# busstop.net
KiCad netlist of a schematic drawn in EAGLE
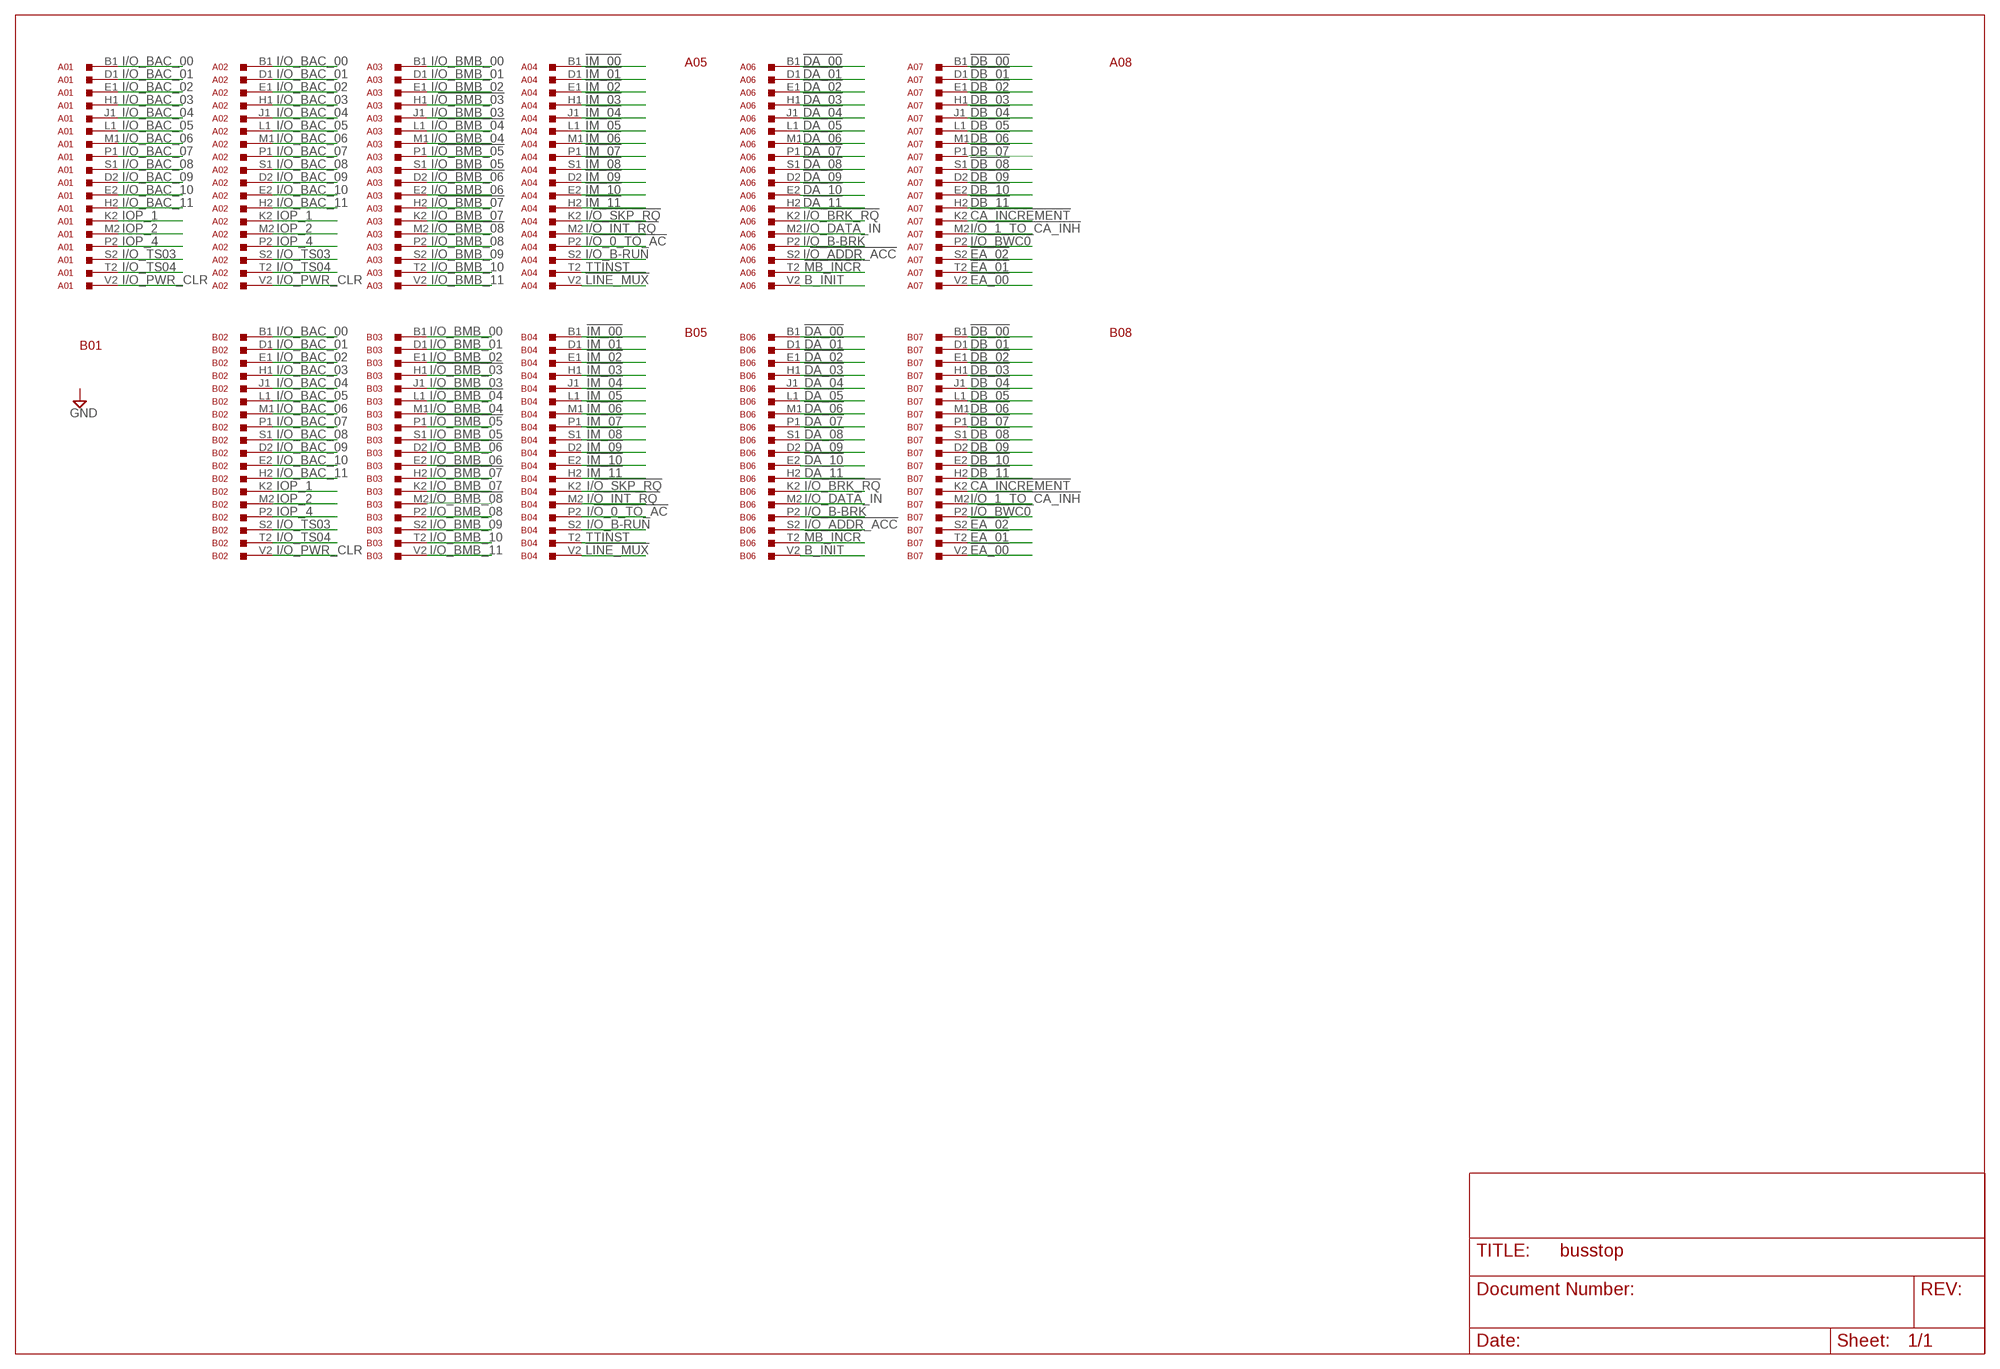
[diagram p0: schematic, sheet 1]

(export (version "E")
  (design (tool "Eeschema 10.0.6"))
  (components
    (comp (ref "A01")
      (value "G717")
      (footprint "eagle-import:H807")
      (libsource (lib "eagle-import") (part "M903"))
    )
    (comp (ref "A02")
      (value "M903")
      (footprint "eagle-import:H807")
      (libsource (lib "eagle-import") (part "M903"))
    )
    (comp (ref "A03")
      (value "M903")
      (footprint "eagle-import:H807")
      (libsource (lib "eagle-import") (part "M903"))
    )
    (comp (ref "A04")
      (value "M903")
      (footprint "eagle-import:H807")
      (libsource (lib "eagle-import") (part "M903"))
    )
    (comp (ref "A05")
      (value "H807")
      (footprint "eagle-import:H807")
      (libsource (lib "eagle-import") (part "H807"))
    )
    (comp (ref "A06")
      (value "M903")
      (footprint "eagle-import:H807")
      (libsource (lib "eagle-import") (part "M903"))
    )
    (comp (ref "A07")
      (value "M903")
      (footprint "eagle-import:H807")
      (libsource (lib "eagle-import") (part "M903"))
    )
    (comp (ref "A08")
      (value "H807")
      (footprint "eagle-import:H807")
      (libsource (lib "eagle-import") (part "H807"))
    )
    (comp (ref "B01")
      (value "H807")
      (footprint "eagle-import:H807")
      (libsource (lib "eagle-import") (part "H807"))
    )
    (comp (ref "B02")
      (value "M903")
      (footprint "eagle-import:H807")
      (libsource (lib "eagle-import") (part "M903"))
    )
    (comp (ref "B03")
      (value "M903")
      (footprint "eagle-import:H807")
      (libsource (lib "eagle-import") (part "M903"))
    )
    (comp (ref "B04")
      (value "M903")
      (footprint "eagle-import:H807")
      (libsource (lib "eagle-import") (part "M903"))
    )
    (comp (ref "B05")
      (value "H807")
      (footprint "eagle-import:H807")
      (libsource (lib "eagle-import") (part "H807"))
    )
    (comp (ref "B06")
      (value "M903")
      (footprint "eagle-import:H807")
      (libsource (lib "eagle-import") (part "M903"))
    )
    (comp (ref "B07")
      (value "M903")
      (footprint "eagle-import:H807")
      (libsource (lib "eagle-import") (part "M903"))
    )
    (comp (ref "B08")
      (value "H807")
      (footprint "eagle-import:H807")
      (libsource (lib "eagle-import") (part "H807"))
    )
  )
  (nets
    (net (code "1") (name "/B_INIT") (class "Default")
      (node (ref "A06") (pin "V2") (pinfunction "P$2_V2") (pintype "bidirectional"))
      (node (ref "B06") (pin "V2") (pinfunction "P$2_V2") (pintype "bidirectional"))
    )
    (net (code "2") (name "/IOP_1") (class "Default")
      (node (ref "A01") (pin "K2") (pinfunction "P$2_K2") (pintype "bidirectional"))
      (node (ref "A02") (pin "K2") (pinfunction "P$2_K2") (pintype "bidirectional"))
      (node (ref "B02") (pin "K2") (pinfunction "P$2_K2") (pintype "bidirectional"))
    )
    (net (code "3") (name "/IOP_2") (class "Default")
      (node (ref "A01") (pin "M2") (pinfunction "P$2_M2") (pintype "bidirectional"))
      (node (ref "A02") (pin "M2") (pinfunction "P$2_M2") (pintype "bidirectional"))
      (node (ref "B02") (pin "M2") (pinfunction "P$2_M2") (pintype "bidirectional"))
    )
    (net (code "4") (name "/IOP_4") (class "Default")
      (node (ref "A01") (pin "P2") (pinfunction "P$2_P2") (pintype "bidirectional"))
      (node (ref "A02") (pin "P2") (pinfunction "P$2_P2") (pintype "bidirectional"))
      (node (ref "B02") (pin "P2") (pinfunction "P$2_P2") (pintype "bidirectional"))
    )
    (net (code "5") (name "/I{slash}O_B-BRK") (class "Default")
      (node (ref "A06") (pin "P2") (pinfunction "P$2_P2") (pintype "bidirectional"))
      (node (ref "B06") (pin "P2") (pinfunction "P$2_P2") (pintype "bidirectional"))
    )
    (net (code "6") (name "/I{slash}O_B-RUN") (class "Default")
      (node (ref "A04") (pin "S2") (pinfunction "P$2_S2") (pintype "bidirectional"))
      (node (ref "B04") (pin "S2") (pinfunction "P$2_S2") (pintype "bidirectional"))
    )
    (net (code "7") (name "/I{slash}O_BAC_00") (class "Default")
      (node (ref "A01") (pin "B1") (pinfunction "P$2_B1") (pintype "bidirectional"))
      (node (ref "A02") (pin "B1") (pinfunction "P$2_B1") (pintype "bidirectional"))
      (node (ref "B02") (pin "B1") (pinfunction "P$2_B1") (pintype "bidirectional"))
    )
    (net (code "8") (name "/I{slash}O_BAC_01") (class "Default")
      (node (ref "A01") (pin "D1") (pinfunction "P$2_D1") (pintype "bidirectional"))
      (node (ref "A02") (pin "D1") (pinfunction "P$2_D1") (pintype "bidirectional"))
      (node (ref "B02") (pin "D1") (pinfunction "P$2_D1") (pintype "bidirectional"))
    )
    (net (code "9") (name "/I{slash}O_BAC_02") (class "Default")
      (node (ref "A01") (pin "E1") (pinfunction "P$2_E1") (pintype "bidirectional"))
      (node (ref "A02") (pin "E1") (pinfunction "P$2_E1") (pintype "bidirectional"))
      (node (ref "B02") (pin "E1") (pinfunction "P$2_E1") (pintype "bidirectional"))
    )
    (net (code "10") (name "/I{slash}O_BAC_03") (class "Default")
      (node (ref "A01") (pin "H1") (pinfunction "P$2_H1") (pintype "bidirectional"))
      (node (ref "A02") (pin "H1") (pinfunction "P$2_H1") (pintype "bidirectional"))
      (node (ref "B02") (pin "H1") (pinfunction "P$2_H1") (pintype "bidirectional"))
    )
    (net (code "11") (name "/I{slash}O_BAC_04") (class "Default")
      (node (ref "A01") (pin "J1") (pinfunction "P$2_J1") (pintype "bidirectional"))
      (node (ref "A02") (pin "J1") (pinfunction "P$2_J1") (pintype "bidirectional"))
      (node (ref "B02") (pin "J1") (pinfunction "P$2_J1") (pintype "bidirectional"))
    )
    (net (code "12") (name "/I{slash}O_BAC_05") (class "Default")
      (node (ref "A01") (pin "L1") (pinfunction "P$2_L1") (pintype "bidirectional"))
      (node (ref "A02") (pin "L1") (pinfunction "P$2_L1") (pintype "bidirectional"))
      (node (ref "B02") (pin "L1") (pinfunction "P$2_L1") (pintype "bidirectional"))
    )
    (net (code "13") (name "/I{slash}O_BAC_06") (class "Default")
      (node (ref "A01") (pin "M1") (pinfunction "P$2_M1") (pintype "bidirectional"))
      (node (ref "A02") (pin "M1") (pinfunction "P$2_M1") (pintype "bidirectional"))
      (node (ref "B02") (pin "M1") (pinfunction "P$2_M1") (pintype "bidirectional"))
    )
    (net (code "14") (name "/I{slash}O_BAC_07") (class "Default")
      (node (ref "A01") (pin "P1") (pinfunction "P$2_P1") (pintype "bidirectional"))
      (node (ref "A02") (pin "P1") (pinfunction "P$2_P1") (pintype "bidirectional"))
      (node (ref "B02") (pin "P1") (pinfunction "P$2_P1") (pintype "bidirectional"))
    )
    (net (code "15") (name "/I{slash}O_BAC_08") (class "Default")
      (node (ref "A01") (pin "S1") (pinfunction "P$2_S1") (pintype "bidirectional"))
      (node (ref "A02") (pin "S1") (pinfunction "P$2_S1") (pintype "bidirectional"))
      (node (ref "B02") (pin "S1") (pinfunction "P$2_S1") (pintype "bidirectional"))
    )
    (net (code "16") (name "/I{slash}O_BAC_09") (class "Default")
      (node (ref "A01") (pin "D2") (pinfunction "P$2_D2") (pintype "bidirectional"))
      (node (ref "A02") (pin "D2") (pinfunction "P$2_D2") (pintype "bidirectional"))
      (node (ref "B02") (pin "D2") (pinfunction "P$2_D2") (pintype "bidirectional"))
    )
    (net (code "17") (name "/I{slash}O_BAC_10") (class "Default")
      (node (ref "A01") (pin "E2") (pinfunction "P$2_E2") (pintype "bidirectional"))
      (node (ref "A02") (pin "E2") (pinfunction "P$2_E2") (pintype "bidirectional"))
      (node (ref "B02") (pin "E2") (pinfunction "P$2_E2") (pintype "bidirectional"))
    )
    (net (code "18") (name "/I{slash}O_BAC_11") (class "Default")
      (node (ref "A01") (pin "H2") (pinfunction "P$2_H2") (pintype "bidirectional"))
      (node (ref "A02") (pin "H2") (pinfunction "P$2_H2") (pintype "bidirectional"))
      (node (ref "B02") (pin "H2") (pinfunction "P$2_H2") (pintype "bidirectional"))
    )
    (net (code "19") (name "/I{slash}O_BMB_00") (class "Default")
      (node (ref "A03") (pin "B1") (pinfunction "P$2_B1") (pintype "bidirectional"))
      (node (ref "B03") (pin "B1") (pinfunction "P$2_B1") (pintype "bidirectional"))
    )
    (net (code "20") (name "/I{slash}O_BMB_01") (class "Default")
      (node (ref "A03") (pin "D1") (pinfunction "P$2_D1") (pintype "bidirectional"))
      (node (ref "B03") (pin "D1") (pinfunction "P$2_D1") (pintype "bidirectional"))
    )
    (net (code "21") (name "/I{slash}O_BMB_02") (class "Default")
      (node (ref "A03") (pin "E1") (pinfunction "P$2_E1") (pintype "bidirectional"))
      (node (ref "B03") (pin "E1") (pinfunction "P$2_E1") (pintype "bidirectional"))
    )
    (net (code "22") (name "/I{slash}O_BMB_03") (class "Default")
      (node (ref "A03") (pin "J1") (pinfunction "P$2_J1") (pintype "bidirectional"))
      (node (ref "B03") (pin "J1") (pinfunction "P$2_J1") (pintype "bidirectional"))
    )
    (net (code "23") (name "/I{slash}O_BMB_04") (class "Default")
      (node (ref "A03") (pin "M1") (pinfunction "P$2_M1") (pintype "bidirectional"))
      (node (ref "B03") (pin "M1") (pinfunction "P$2_M1") (pintype "bidirectional"))
    )
    (net (code "24") (name "/I{slash}O_BMB_05") (class "Default")
      (node (ref "A03") (pin "S1") (pinfunction "P$2_S1") (pintype "bidirectional"))
      (node (ref "B03") (pin "S1") (pinfunction "P$2_S1") (pintype "bidirectional"))
    )
    (net (code "25") (name "/I{slash}O_BMB_06") (class "Default")
      (node (ref "A03") (pin "E2") (pinfunction "P$2_E2") (pintype "bidirectional"))
      (node (ref "B03") (pin "E2") (pinfunction "P$2_E2") (pintype "bidirectional"))
    )
    (net (code "26") (name "/I{slash}O_BMB_07") (class "Default")
      (node (ref "A03") (pin "K2") (pinfunction "P$2_K2") (pintype "bidirectional"))
      (node (ref "B03") (pin "K2") (pinfunction "P$2_K2") (pintype "bidirectional"))
    )
    (net (code "27") (name "/I{slash}O_BMB_08") (class "Default")
      (node (ref "A03") (pin "P2") (pinfunction "P$2_P2") (pintype "bidirectional"))
      (node (ref "B03") (pin "P2") (pinfunction "P$2_P2") (pintype "bidirectional"))
    )
    (net (code "28") (name "/I{slash}O_BMB_09") (class "Default")
      (node (ref "A03") (pin "S2") (pinfunction "P$2_S2") (pintype "bidirectional"))
      (node (ref "B03") (pin "S2") (pinfunction "P$2_S2") (pintype "bidirectional"))
    )
    (net (code "29") (name "/I{slash}O_BMB_10") (class "Default")
      (node (ref "A03") (pin "T2") (pinfunction "P$2_T2") (pintype "bidirectional"))
      (node (ref "B03") (pin "T2") (pinfunction "P$2_T2") (pintype "bidirectional"))
    )
    (net (code "30") (name "/I{slash}O_BMB_11") (class "Default")
      (node (ref "A03") (pin "V2") (pinfunction "P$2_V2") (pintype "bidirectional"))
      (node (ref "B03") (pin "V2") (pinfunction "P$2_V2") (pintype "bidirectional"))
    )
    (net (code "31") (name "/I{slash}O_DATA_IN") (class "Default")
      (node (ref "A06") (pin "M2") (pinfunction "P$2_M2") (pintype "bidirectional"))
      (node (ref "B06") (pin "M2") (pinfunction "P$2_M2") (pintype "bidirectional"))
    )
    (net (code "32") (name "/I{slash}O_PWR_CLR") (class "Default")
      (node (ref "A01") (pin "V2") (pinfunction "P$2_V2") (pintype "bidirectional"))
      (node (ref "A02") (pin "V2") (pinfunction "P$2_V2") (pintype "bidirectional"))
      (node (ref "B02") (pin "V2") (pinfunction "P$2_V2") (pintype "bidirectional"))
    )
    (net (code "33") (name "/I{slash}O_TS03") (class "Default")
      (node (ref "A01") (pin "S2") (pinfunction "P$2_S2") (pintype "bidirectional"))
      (node (ref "A02") (pin "S2") (pinfunction "P$2_S2") (pintype "bidirectional"))
      (node (ref "B02") (pin "S2") (pinfunction "P$2_S2") (pintype "bidirectional"))
    )
    (net (code "34") (name "/I{slash}O_TS04") (class "Default")
      (node (ref "A01") (pin "T2") (pinfunction "P$2_T2") (pintype "bidirectional"))
      (node (ref "A02") (pin "T2") (pinfunction "P$2_T2") (pintype "bidirectional"))
      (node (ref "B02") (pin "T2") (pinfunction "P$2_T2") (pintype "bidirectional"))
    )
    (net (code "35") (name "/I{slash}~{O_0_TO_AC}") (class "Default")
      (node (ref "A04") (pin "P2") (pinfunction "P$2_P2") (pintype "bidirectional"))
      (node (ref "B04") (pin "P2") (pinfunction "P$2_P2") (pintype "bidirectional"))
    )
    (net (code "36") (name "/I{slash}~{O_1_TO_CA_INH}") (class "Default")
      (node (ref "A07") (pin "M2") (pinfunction "P$2_M2") (pintype "bidirectional"))
      (node (ref "B07") (pin "M2") (pinfunction "P$2_M2") (pintype "bidirectional"))
    )
    (net (code "37") (name "/I{slash}~{O_ADDR_ACC}") (class "Default")
      (node (ref "A06") (pin "S2") (pinfunction "P$2_S2") (pintype "bidirectional"))
      (node (ref "B06") (pin "S2") (pinfunction "P$2_S2") (pintype "bidirectional"))
    )
    (net (code "38") (name "/I{slash}~{O_BMB_03}") (class "Default")
      (node (ref "A03") (pin "H1") (pinfunction "P$2_H1") (pintype "bidirectional"))
      (node (ref "B03") (pin "H1") (pinfunction "P$2_H1") (pintype "bidirectional"))
    )
    (net (code "39") (name "/I{slash}~{O_BMB_04}") (class "Default")
      (node (ref "A03") (pin "L1") (pinfunction "P$2_L1") (pintype "bidirectional"))
      (node (ref "B03") (pin "L1") (pinfunction "P$2_L1") (pintype "bidirectional"))
    )
    (net (code "40") (name "/I{slash}~{O_BMB_05}") (class "Default")
      (node (ref "A03") (pin "P1") (pinfunction "P$2_P1") (pintype "bidirectional"))
      (node (ref "B03") (pin "P1") (pinfunction "P$2_P1") (pintype "bidirectional"))
    )
    (net (code "41") (name "/I{slash}~{O_BMB_06}") (class "Default")
      (node (ref "A03") (pin "D2") (pinfunction "P$2_D2") (pintype "bidirectional"))
      (node (ref "B03") (pin "D2") (pinfunction "P$2_D2") (pintype "bidirectional"))
    )
    (net (code "42") (name "/I{slash}~{O_BMB_07}") (class "Default")
      (node (ref "A03") (pin "H2") (pinfunction "P$2_H2") (pintype "bidirectional"))
      (node (ref "B03") (pin "H2") (pinfunction "P$2_H2") (pintype "bidirectional"))
    )
    (net (code "43") (name "/I{slash}~{O_BMB_08}") (class "Default")
      (node (ref "A03") (pin "M2") (pinfunction "P$2_M2") (pintype "bidirectional"))
      (node (ref "B03") (pin "M2") (pinfunction "P$2_M2") (pintype "bidirectional"))
    )
    (net (code "44") (name "/I{slash}~{O_BRK_RQ}") (class "Default")
      (node (ref "A06") (pin "K2") (pinfunction "P$2_K2") (pintype "bidirectional"))
      (node (ref "B06") (pin "K2") (pinfunction "P$2_K2") (pintype "bidirectional"))
    )
    (net (code "45") (name "/I{slash}~{O_BWC0}") (class "Default")
      (node (ref "A07") (pin "P2") (pinfunction "P$2_P2") (pintype "bidirectional"))
      (node (ref "B07") (pin "P2") (pinfunction "P$2_P2") (pintype "bidirectional"))
    )
    (net (code "46") (name "/I{slash}~{O_INT_RQ}") (class "Default")
      (node (ref "A04") (pin "M2") (pinfunction "P$2_M2") (pintype "bidirectional"))
      (node (ref "B04") (pin "M2") (pinfunction "P$2_M2") (pintype "bidirectional"))
    )
    (net (code "47") (name "/I{slash}~{O_SKP_RQ}") (class "Default")
      (node (ref "A04") (pin "K2") (pinfunction "P$2_K2") (pintype "bidirectional"))
      (node (ref "B04") (pin "K2") (pinfunction "P$2_K2") (pintype "bidirectional"))
    )
    (net (code "48") (name "/TTINST") (class "Default")
      (node (ref "A04") (pin "T2") (pinfunction "P$2_T2") (pintype "bidirectional"))
      (node (ref "B04") (pin "T2") (pinfunction "P$2_T2") (pintype "bidirectional"))
    )
    (net (code "49") (name "/~{CA_INCREMENT}") (class "Default")
      (node (ref "A07") (pin "K2") (pinfunction "P$2_K2") (pintype "bidirectional"))
      (node (ref "B07") (pin "K2") (pinfunction "P$2_K2") (pintype "bidirectional"))
    )
    (net (code "50") (name "/~{DA_00}") (class "Default")
      (node (ref "A06") (pin "B1") (pinfunction "P$2_B1") (pintype "bidirectional"))
      (node (ref "B06") (pin "B1") (pinfunction "P$2_B1") (pintype "bidirectional"))
    )
    (net (code "51") (name "/~{DA_01}") (class "Default")
      (node (ref "A06") (pin "D1") (pinfunction "P$2_D1") (pintype "bidirectional"))
      (node (ref "B06") (pin "D1") (pinfunction "P$2_D1") (pintype "bidirectional"))
    )
    (net (code "52") (name "/~{DA_02}") (class "Default")
      (node (ref "A06") (pin "E1") (pinfunction "P$2_E1") (pintype "bidirectional"))
      (node (ref "B06") (pin "E1") (pinfunction "P$2_E1") (pintype "bidirectional"))
    )
    (net (code "53") (name "/~{DA_03}") (class "Default")
      (node (ref "A06") (pin "H1") (pinfunction "P$2_H1") (pintype "bidirectional"))
      (node (ref "B06") (pin "H1") (pinfunction "P$2_H1") (pintype "bidirectional"))
    )
    (net (code "54") (name "/~{DA_04}") (class "Default")
      (node (ref "A06") (pin "J1") (pinfunction "P$2_J1") (pintype "bidirectional"))
      (node (ref "B06") (pin "J1") (pinfunction "P$2_J1") (pintype "bidirectional"))
    )
    (net (code "55") (name "/~{DA_05}") (class "Default")
      (node (ref "A06") (pin "L1") (pinfunction "P$2_L1") (pintype "bidirectional"))
      (node (ref "B06") (pin "L1") (pinfunction "P$2_L1") (pintype "bidirectional"))
    )
    (net (code "56") (name "/~{DA_06}") (class "Default")
      (node (ref "A06") (pin "M1") (pinfunction "P$2_M1") (pintype "bidirectional"))
      (node (ref "B06") (pin "M1") (pinfunction "P$2_M1") (pintype "bidirectional"))
    )
    (net (code "57") (name "/~{DA_07}") (class "Default")
      (node (ref "A06") (pin "P1") (pinfunction "P$2_P1") (pintype "bidirectional"))
      (node (ref "B06") (pin "P1") (pinfunction "P$2_P1") (pintype "bidirectional"))
    )
    (net (code "58") (name "/~{DA_08}") (class "Default")
      (node (ref "A06") (pin "S1") (pinfunction "P$2_S1") (pintype "bidirectional"))
      (node (ref "B06") (pin "S1") (pinfunction "P$2_S1") (pintype "bidirectional"))
    )
    (net (code "59") (name "/~{DA_09}") (class "Default")
      (node (ref "A06") (pin "D2") (pinfunction "P$2_D2") (pintype "bidirectional"))
      (node (ref "B06") (pin "D2") (pinfunction "P$2_D2") (pintype "bidirectional"))
    )
    (net (code "60") (name "/~{DA_10}") (class "Default")
      (node (ref "A06") (pin "E2") (pinfunction "P$2_E2") (pintype "bidirectional"))
      (node (ref "B06") (pin "E2") (pinfunction "P$2_E2") (pintype "bidirectional"))
    )
    (net (code "61") (name "/~{DA_11}") (class "Default")
      (node (ref "A06") (pin "H2") (pinfunction "P$2_H2") (pintype "bidirectional"))
      (node (ref "B06") (pin "H2") (pinfunction "P$2_H2") (pintype "bidirectional"))
    )
    (net (code "62") (name "/~{DB_00}") (class "Default")
      (node (ref "A07") (pin "B1") (pinfunction "P$2_B1") (pintype "bidirectional"))
      (node (ref "B07") (pin "B1") (pinfunction "P$2_B1") (pintype "bidirectional"))
    )
    (net (code "63") (name "/~{DB_01}") (class "Default")
      (node (ref "A07") (pin "D1") (pinfunction "P$2_D1") (pintype "bidirectional"))
      (node (ref "B07") (pin "D1") (pinfunction "P$2_D1") (pintype "bidirectional"))
    )
    (net (code "64") (name "/~{DB_02}") (class "Default")
      (node (ref "A07") (pin "E1") (pinfunction "P$2_E1") (pintype "bidirectional"))
      (node (ref "B07") (pin "E1") (pinfunction "P$2_E1") (pintype "bidirectional"))
    )
    (net (code "65") (name "/~{DB_03}") (class "Default")
      (node (ref "A07") (pin "H1") (pinfunction "P$2_H1") (pintype "bidirectional"))
      (node (ref "B07") (pin "H1") (pinfunction "P$2_H1") (pintype "bidirectional"))
    )
    (net (code "66") (name "/~{DB_04}") (class "Default")
      (node (ref "A07") (pin "J1") (pinfunction "P$2_J1") (pintype "bidirectional"))
      (node (ref "B07") (pin "J1") (pinfunction "P$2_J1") (pintype "bidirectional"))
    )
    (net (code "67") (name "/~{DB_05}") (class "Default")
      (node (ref "A07") (pin "L1") (pinfunction "P$2_L1") (pintype "bidirectional"))
      (node (ref "B07") (pin "L1") (pinfunction "P$2_L1") (pintype "bidirectional"))
    )
    (net (code "68") (name "/~{DB_06}") (class "Default")
      (node (ref "A07") (pin "M1") (pinfunction "P$2_M1") (pintype "bidirectional"))
      (node (ref "B07") (pin "M1") (pinfunction "P$2_M1") (pintype "bidirectional"))
    )
    (net (code "69") (name "/~{DB_07}") (class "Default")
      (node (ref "A07") (pin "P1") (pinfunction "P$2_P1") (pintype "bidirectional"))
      (node (ref "B07") (pin "P1") (pinfunction "P$2_P1") (pintype "bidirectional"))
    )
    (net (code "70") (name "/~{DB_08}") (class "Default")
      (node (ref "A07") (pin "S1") (pinfunction "P$2_S1") (pintype "bidirectional"))
      (node (ref "B07") (pin "S1") (pinfunction "P$2_S1") (pintype "bidirectional"))
    )
    (net (code "71") (name "/~{DB_09}") (class "Default")
      (node (ref "A07") (pin "D2") (pinfunction "P$2_D2") (pintype "bidirectional"))
      (node (ref "B07") (pin "D2") (pinfunction "P$2_D2") (pintype "bidirectional"))
    )
    (net (code "72") (name "/~{DB_10}") (class "Default")
      (node (ref "A07") (pin "E2") (pinfunction "P$2_E2") (pintype "bidirectional"))
      (node (ref "B07") (pin "E2") (pinfunction "P$2_E2") (pintype "bidirectional"))
    )
    (net (code "73") (name "/~{DB_11}") (class "Default")
      (node (ref "A07") (pin "H2") (pinfunction "P$2_H2") (pintype "bidirectional"))
      (node (ref "B07") (pin "H2") (pinfunction "P$2_H2") (pintype "bidirectional"))
    )
    (net (code "74") (name "/~{EA_00}") (class "Default")
      (node (ref "A07") (pin "V2") (pinfunction "P$2_V2") (pintype "bidirectional"))
      (node (ref "B07") (pin "V2") (pinfunction "P$2_V2") (pintype "bidirectional"))
    )
    (net (code "75") (name "/~{EA_01}") (class "Default")
      (node (ref "A07") (pin "T2") (pinfunction "P$2_T2") (pintype "bidirectional"))
      (node (ref "B07") (pin "T2") (pinfunction "P$2_T2") (pintype "bidirectional"))
    )
    (net (code "76") (name "/~{EA_02}") (class "Default")
      (node (ref "A07") (pin "S2") (pinfunction "P$2_S2") (pintype "bidirectional"))
      (node (ref "B07") (pin "S2") (pinfunction "P$2_S2") (pintype "bidirectional"))
    )
    (net (code "77") (name "/~{IM_00}") (class "Default")
      (node (ref "A04") (pin "B1") (pinfunction "P$2_B1") (pintype "bidirectional"))
      (node (ref "B04") (pin "B1") (pinfunction "P$2_B1") (pintype "bidirectional"))
    )
    (net (code "78") (name "/~{IM_01}") (class "Default")
      (node (ref "A04") (pin "D1") (pinfunction "P$2_D1") (pintype "bidirectional"))
      (node (ref "B04") (pin "D1") (pinfunction "P$2_D1") (pintype "bidirectional"))
    )
    (net (code "79") (name "/~{IM_02}") (class "Default")
      (node (ref "A04") (pin "E1") (pinfunction "P$2_E1") (pintype "bidirectional"))
      (node (ref "B04") (pin "E1") (pinfunction "P$2_E1") (pintype "bidirectional"))
    )
    (net (code "80") (name "/~{IM_03}") (class "Default")
      (node (ref "A04") (pin "H1") (pinfunction "P$2_H1") (pintype "bidirectional"))
      (node (ref "B04") (pin "H1") (pinfunction "P$2_H1") (pintype "bidirectional"))
    )
    (net (code "81") (name "/~{IM_04}") (class "Default")
      (node (ref "A04") (pin "J1") (pinfunction "P$2_J1") (pintype "bidirectional"))
      (node (ref "B04") (pin "J1") (pinfunction "P$2_J1") (pintype "bidirectional"))
    )
    (net (code "82") (name "/~{IM_05}") (class "Default")
      (node (ref "A04") (pin "L1") (pinfunction "P$2_L1") (pintype "bidirectional"))
      (node (ref "B04") (pin "L1") (pinfunction "P$2_L1") (pintype "bidirectional"))
    )
    (net (code "83") (name "/~{IM_06}") (class "Default")
      (node (ref "A04") (pin "M1") (pinfunction "P$2_M1") (pintype "bidirectional"))
      (node (ref "B04") (pin "M1") (pinfunction "P$2_M1") (pintype "bidirectional"))
    )
    (net (code "84") (name "/~{IM_07}") (class "Default")
      (node (ref "A04") (pin "P1") (pinfunction "P$2_P1") (pintype "bidirectional"))
      (node (ref "B04") (pin "P1") (pinfunction "P$2_P1") (pintype "bidirectional"))
    )
    (net (code "85") (name "/~{IM_08}") (class "Default")
      (node (ref "A04") (pin "S1") (pinfunction "P$2_S1") (pintype "bidirectional"))
      (node (ref "B04") (pin "S1") (pinfunction "P$2_S1") (pintype "bidirectional"))
    )
    (net (code "86") (name "/~{IM_09}") (class "Default")
      (node (ref "A04") (pin "D2") (pinfunction "P$2_D2") (pintype "bidirectional"))
      (node (ref "B04") (pin "D2") (pinfunction "P$2_D2") (pintype "bidirectional"))
    )
    (net (code "87") (name "/~{IM_10}") (class "Default")
      (node (ref "A04") (pin "E2") (pinfunction "P$2_E2") (pintype "bidirectional"))
      (node (ref "B04") (pin "E2") (pinfunction "P$2_E2") (pintype "bidirectional"))
    )
    (net (code "88") (name "/~{IM_11}") (class "Default")
      (node (ref "A04") (pin "H2") (pinfunction "P$2_H2") (pintype "bidirectional"))
      (node (ref "B04") (pin "H2") (pinfunction "P$2_H2") (pintype "bidirectional"))
    )
    (net (code "89") (name "/~{LINE_MUX}") (class "Default")
      (node (ref "A04") (pin "V2") (pinfunction "P$2_V2") (pintype "bidirectional"))
      (node (ref "B04") (pin "V2") (pinfunction "P$2_V2") (pintype "bidirectional"))
    )
    (net (code "90") (name "/~{MB_INCR}") (class "Default")
      (node (ref "A06") (pin "T2") (pinfunction "P$2_T2") (pintype "bidirectional"))
      (node (ref "B06") (pin "T2") (pinfunction "P$2_T2") (pintype "bidirectional"))
    )
  )
)
